# Accelerometer.net
KiCad netlist of a schematic drawn in Altium Designer
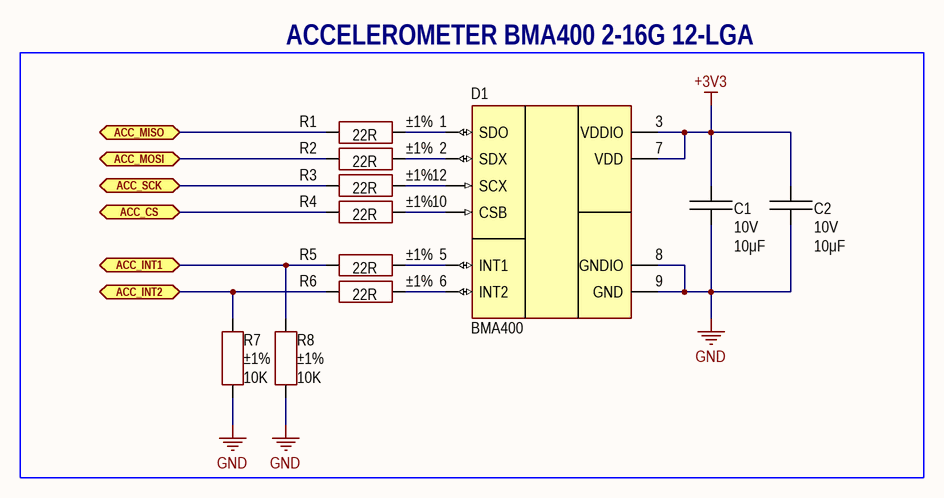
[diagram p0: Accelerometer.SchDoc]

(export (version "E")
  (design (tool "Eeschema 10.0.6"))
  (components
    (comp (ref "C1")
      (value "10μF")
      (footprint "CAP: 0805")
      (description "10 µF ±10% 10V Ceramic Capacitor X7R 0805 (2012 Metric)")
      (fields
        (field (name "MANUFACTURER") "Yageo")
        (field (name "PARTNUMBER") "CC0805KFX7R6BB106")
        (field (name "VOLTAGE") "10V")
      )
      (libsource (lib "capacitor") (part "Ceramic_0805"))
    )
    (comp (ref "C2")
      (value "10μF")
      (footprint "CAP: 0805")
      (description "10 µF ±10% 10V Ceramic Capacitor X7R 0805 (2012 Metric)")
      (fields
        (field (name "MANUFACTURER") "Yageo")
        (field (name "PARTNUMBER") "CC0805KFX7R6BB106")
        (field (name "VOLTAGE") "10V")
      )
      (libsource (lib "capacitor") (part "Ceramic_0805"))
    )
    (comp (ref "D1")
      (value "~")
      (footprint "12-VFLGA")
      (description "Accelerometer")
      (fields
        (field (name "MANUFACTURER") "Bosch Sensortec")
        (field (name "VALUEMANUFACTURERPARTNUMBER") "IC accelerometer, Digital sensor, , , , -40...+85°C, 12-VFLGA")
        (field (name "PARTNUMBER") "BMA400")
      )
      (libsource (lib "MyLib") (part "BMA400"))
    )
    (comp (ref "R1")
      (value "22R")
      (footprint "RES: 0805")
      (description "22 Ohms ±1% 0.125W, 1/8W Chip Resistor 0805 (2012 Metric) Moisture Resistant Thick Film")
      (fields
        (field (name "MANUFACTURER") "Yageo")
        (field (name "PARTNUMBER") "RC0805FR-0722RL")
        (field (name "TOLERANCE") "±1%")
      )
      (libsource (lib "resistor") (part "Resistor_0805"))
    )
    (comp (ref "R2")
      (value "22R")
      (footprint "RES: 0805")
      (description "22 Ohms ±1% 0.125W, 1/8W Chip Resistor 0805 (2012 Metric) Moisture Resistant Thick Film")
      (fields
        (field (name "MANUFACTURER") "Yageo")
        (field (name "PARTNUMBER") "RC0805FR-0722RL")
        (field (name "TOLERANCE") "±1%")
      )
      (libsource (lib "resistor") (part "Resistor_0805"))
    )
    (comp (ref "R3")
      (value "22R")
      (footprint "RES: 0805")
      (description "22 Ohms ±1% 0.125W, 1/8W Chip Resistor 0805 (2012 Metric) Moisture Resistant Thick Film")
      (fields
        (field (name "MANUFACTURER") "Yageo")
        (field (name "PARTNUMBER") "RC0805FR-0722RL")
        (field (name "TOLERANCE") "±1%")
      )
      (libsource (lib "resistor") (part "Resistor_0805"))
    )
    (comp (ref "R4")
      (value "22R")
      (footprint "RES: 0805")
      (description "22 Ohms ±1% 0.125W, 1/8W Chip Resistor 0805 (2012 Metric) Moisture Resistant Thick Film")
      (fields
        (field (name "MANUFACTURER") "Yageo")
        (field (name "PARTNUMBER") "RC0805FR-0722RL")
        (field (name "TOLERANCE") "±1%")
      )
      (libsource (lib "resistor") (part "Resistor_0805"))
    )
    (comp (ref "R5")
      (value "22R")
      (footprint "RES: 0805")
      (description "22 Ohms ±1% 0.125W, 1/8W Chip Resistor 0805 (2012 Metric) Moisture Resistant Thick Film")
      (fields
        (field (name "MANUFACTURER") "Yageo")
        (field (name "PARTNUMBER") "RC0805FR-0722RL")
        (field (name "TOLERANCE") "±1%")
      )
      (libsource (lib "resistor") (part "Resistor_0805"))
    )
    (comp (ref "R6")
      (value "22R")
      (footprint "RES: 0805")
      (description "22 Ohms ±1% 0.125W, 1/8W Chip Resistor 0805 (2012 Metric) Moisture Resistant Thick Film")
      (fields
        (field (name "MANUFACTURER") "Yageo")
        (field (name "PARTNUMBER") "RC0805FR-0722RL")
        (field (name "TOLERANCE") "±1%")
      )
      (libsource (lib "resistor") (part "Resistor_0805"))
    )
    (comp (ref "R7")
      (value "10K")
      (footprint "RES: 0805")
      (description "10 kOhms ±1% 0.125W, 1/8W Chip Resistor 0805 (2012 Metric) Moisture Resistant Thick Film")
      (fields
        (field (name "MANUFACTURER") "Yageo")
        (field (name "PARTNUMBER") "RC0805FR-0710KL")
        (field (name "TOLERANCE") "±1%")
      )
      (libsource (lib "") (part "Resistor_0805_1"))
    )
    (comp (ref "R8")
      (value "10K")
      (footprint "RES: 0805")
      (description "10 kOhms ±1% 0.125W, 1/8W Chip Resistor 0805 (2012 Metric) Moisture Resistant Thick Film")
      (fields
        (field (name "MANUFACTURER") "Yageo")
        (field (name "PARTNUMBER") "RC0805FR-0710KL")
        (field (name "TOLERANCE") "±1%")
      )
      (libsource (lib "") (part "Resistor_0805_1"))
    )
  )
  (nets
    (net (code "1") (name "+3V3") (class "Default")
      (node (ref "C1") (pin "2") (pinfunction "2_2") (pintype "passive"))
      (node (ref "C2") (pin "2") (pinfunction "2_2") (pintype "passive"))
      (node (ref "D1") (pin "3") (pinfunction "VDDIO_3") (pintype "power_in"))
      (node (ref "D1") (pin "7") (pinfunction "VDD_7") (pintype "power_in"))
    )
    (net (code "2") (name "/ACC_CS") (class "Default")
      (node (ref "R4") (pin "1") (pinfunction "1_1") (pintype "passive"))
    )
    (net (code "3") (name "/ACC_INT1") (class "Default")
      (node (ref "R5") (pin "1") (pinfunction "1_1") (pintype "passive"))
      (node (ref "R8") (pin "2") (pinfunction "2_2") (pintype "passive"))
    )
    (net (code "4") (name "/ACC_INT2") (class "Default")
      (node (ref "R6") (pin "1") (pinfunction "1_1") (pintype "passive"))
      (node (ref "R7") (pin "2") (pinfunction "2_2") (pintype "passive"))
    )
    (net (code "5") (name "/ACC_MISO") (class "Default")
      (node (ref "R1") (pin "1") (pinfunction "1_1") (pintype "passive"))
    )
    (net (code "6") (name "/ACC_MOSI") (class "Default")
      (node (ref "R2") (pin "1") (pinfunction "1_1") (pintype "passive"))
    )
    (net (code "7") (name "/ACC_SCK") (class "Default")
      (node (ref "R3") (pin "1") (pinfunction "1_1") (pintype "passive"))
    )
    (net (code "8") (name "GND") (class "Default")
      (node (ref "C1") (pin "1") (pinfunction "1_1") (pintype "passive"))
      (node (ref "C2") (pin "1") (pinfunction "1_1") (pintype "passive"))
      (node (ref "D1") (pin "8") (pinfunction "GNDIO_8") (pintype "power_in"))
      (node (ref "D1") (pin "9") (pinfunction "GND_9") (pintype "power_in"))
      (node (ref "R7") (pin "1") (pinfunction "1_1") (pintype "passive"))
      (node (ref "R8") (pin "1") (pinfunction "1_1") (pintype "passive"))
    )
    (net (code "9") (name "Net-(D1-CSB)") (class "Default")
      (node (ref "D1") (pin "10") (pinfunction "CSB_10") (pintype "input"))
      (node (ref "R4") (pin "2") (pinfunction "2_2") (pintype "passive"))
    )
    (net (code "10") (name "Net-(D1-INT1)") (class "Default")
      (node (ref "D1") (pin "5") (pinfunction "INT1_5") (pintype "bidirectional"))
      (node (ref "R5") (pin "2") (pinfunction "2_2") (pintype "passive"))
    )
    (net (code "11") (name "Net-(D1-INT2)") (class "Default")
      (node (ref "D1") (pin "6") (pinfunction "INT2_6") (pintype "bidirectional"))
      (node (ref "R6") (pin "2") (pinfunction "2_2") (pintype "passive"))
    )
    (net (code "12") (name "Net-(D1-SCX)") (class "Default")
      (node (ref "D1") (pin "12") (pinfunction "SCX_12") (pintype "input"))
      (node (ref "R3") (pin "2") (pinfunction "2_2") (pintype "passive"))
    )
    (net (code "13") (name "Net-(D1-SDO)") (class "Default")
      (node (ref "D1") (pin "1") (pinfunction "SDO_1") (pintype "bidirectional"))
      (node (ref "R1") (pin "2") (pinfunction "2_2") (pintype "passive"))
    )
    (net (code "14") (name "Net-(D1-SDX)") (class "Default")
      (node (ref "D1") (pin "2") (pinfunction "SDX_2") (pintype "bidirectional"))
      (node (ref "R2") (pin "2") (pinfunction "2_2") (pintype "passive"))
    )
  )
)
